# RS485.net
KiCad netlist of a schematic drawn in Altium Designer
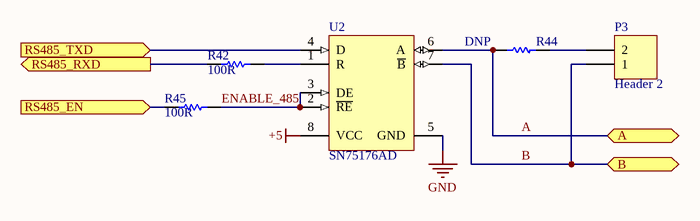
[diagram p0: RS485.SchDoc]

(export (version "E")
  (design (tool "Eeschema 10.0.6"))
  (components
    (comp (ref "P3")
      (value "Header 2")
      (footprint "HDR1X2")
      (description "Header, 2-Pin")
      (fields (field (name "PUBLISHER") "Altium Limited"))
      (libsource (lib "Miscellaneous Connectors") (part "Header 2"))
    )
    (comp (ref "R42")
      (value "100R")
      (footprint "0805")
      (description "Resistor")
      (fields (field (name "POWER") "0.125W"))
      (libsource (lib "PassiveComp") (part "Resistor_SMD"))
    )
    (comp (ref "R44")
      (value "DNP")
      (footprint "0805")
      (description "Resistor")
      (libsource (lib "GeneralLibrary") (part "1-ResistorW"))
    )
    (comp (ref "R45")
      (value "100R")
      (footprint "0805")
      (description "Resistor")
      (fields (field (name "POWER") "0.125W"))
      (libsource (lib "PassiveComp") (part "Resistor_SMD"))
    )
    (comp (ref "U2")
      (value "SN75176AD")
      (footprint "soic-8")
      (fields (field (name "MANUFACTURER") "Texas Instruments"))
      (libsource (lib "Texas Instruments Interface RS-422") (part "SN75176AD"))
    )
  )
  (nets
    (net (code "1") (name "+5") (class "Default")
      (node (ref "U2") (pin "8") (pinfunction "VCC_8") (pintype "power_in"))
    )
    (net (code "2") (name "/A") (class "Default")
      (node (ref "R44") (pin "2") (pinfunction "2_2") (pintype "passive"))
      (node (ref "U2") (pin "6") (pinfunction "A_6") (pintype "bidirectional"))
    )
    (net (code "3") (name "/B") (class "Default")
      (node (ref "P3") (pin "1") (pinfunction "1_1") (pintype "passive"))
      (node (ref "U2") (pin "7") (pinfunction "~{B}_7") (pintype "bidirectional"))
    )
    (net (code "4") (name "/ENABLE_485") (class "Default")
      (node (ref "R45") (pin "2") (pinfunction "2_2") (pintype "passive"))
      (node (ref "U2") (pin "2") (pinfunction "~{RE}_2") (pintype "input"))
      (node (ref "U2") (pin "3") (pinfunction "DE_3") (pintype "input"))
    )
    (net (code "5") (name "/RS485_EN") (class "Default")
      (node (ref "R45") (pin "1") (pinfunction "1_1") (pintype "passive"))
    )
    (net (code "6") (name "/RS485_RXD") (class "Default")
      (node (ref "R42") (pin "1") (pinfunction "1_1") (pintype "passive"))
    )
    (net (code "7") (name "/RS485_TXD") (class "Default")
      (node (ref "U2") (pin "4") (pinfunction "D_4") (pintype "input"))
    )
    (net (code "8") (name "GND") (class "Default")
      (node (ref "U2") (pin "5") (pinfunction "GND_5") (pintype "power_in"))
    )
    (net (code "9") (name "Net-(P3-Pad2)") (class "Default")
      (node (ref "P3") (pin "2") (pinfunction "2_2") (pintype "passive"))
      (node (ref "R44") (pin "1") (pinfunction "1_1") (pintype "passive"))
    )
    (net (code "10") (name "Net-(U2-R)") (class "Default")
      (node (ref "R42") (pin "2") (pinfunction "2_2") (pintype "passive"))
      (node (ref "U2") (pin "1") (pinfunction "R_1") (pintype "tri_state"))
    )
  )
)
